# Iso_SPI_PHY.net
KiCad netlist of a schematic drawn in Altium Designer
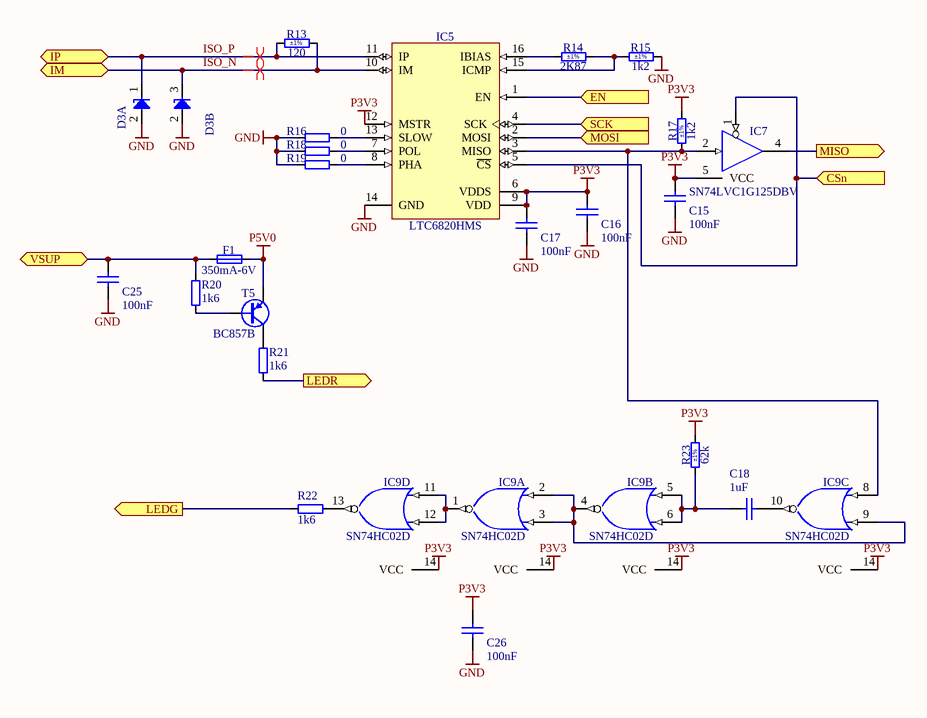
[diagram p0: Iso_SPI_PHY.SchDoc]

(export (version "E")
  (design (tool "Eeschema 10.0.6"))
  (components
    (comp (ref "C15")
      (value "100nF")
      (footprint "CAPC1005X55N")
      (description "Non-polarised capacitor")
      (fields
        (field (name "PART NUMBER") "CC0402_100NF_50V_10%_X7R")
        (field (name "VOLTAGE") "50V")
        (field (name "AUTHOR") "CERN DEM MR")
      )
      (libsource (lib "Capacitors") (part "Capacitor - non polarized"))
    )
    (comp (ref "C16")
      (value "100nF")
      (footprint "CAPC1005X55N")
      (description "Non-polarised capacitor")
      (fields
        (field (name "PART NUMBER") "CC0402_100NF_50V_10%_X7R")
        (field (name "VOLTAGE") "50V")
        (field (name "AUTHOR") "CERN DEM MR")
      )
      (libsource (lib "Capacitors") (part "Capacitor - non polarized"))
    )
    (comp (ref "C17")
      (value "100nF")
      (footprint "CAPC1005X55N")
      (description "Non-polarised capacitor")
      (fields
        (field (name "PART NUMBER") "CC0402_100NF_50V_10%_X7R")
        (field (name "VOLTAGE") "50V")
        (field (name "AUTHOR") "CERN DEM MR")
      )
      (libsource (lib "Capacitors") (part "Capacitor - non polarized"))
    )
    (comp (ref "C18")
      (value "1uF")
      (footprint "CAPC1608X87N")
      (description "Non-polarised capacitor")
      (fields
        (field (name "PART NUMBER") "CC0603_1UF_25V_10%_X7R")
        (field (name "VOLTAGE") "25V")
        (field (name "AUTHOR") "CERN DEM JLC")
      )
      (libsource (lib "Capacitors") (part "Capacitor - non polarized"))
    )
    (comp (ref "C25")
      (value "100nF")
      (footprint "CAPC1005X55N")
      (description "Non-polarised capacitor")
      (fields
        (field (name "PART NUMBER") "CC0402_100NF_50V_10%_X7R")
        (field (name "VOLTAGE") "50V")
        (field (name "AUTHOR") "CERN DEM MR")
      )
      (libsource (lib "Capacitors") (part "Capacitor - non polarized"))
    )
    (comp (ref "C26")
      (value "100nF")
      (footprint "CAPC1005X55N")
      (description "Non-polarised capacitor")
      (fields
        (field (name "PART NUMBER") "CC0402_100NF_50V_10%_X7R")
        (field (name "VOLTAGE") "50V")
        (field (name "AUTHOR") "CERN DEM MR")
      )
      (libsource (lib "Capacitors") (part "Capacitor - non polarized"))
    )
    (comp (ref "D3")
      (value "PESD3V3L5UY")
      (footprint "SOT65P210X110-6N")
      (description "Fivefold ESD Protection Diode Arrays")
      (fields
        (field (name "VOLTAGE") "3.3V")
        (field (name "POWER") "200W")
        (field (name "AUTHOR") "CERN DEM WB")
      )
      (libsource (lib "ICs And Semiconductors") (part "PESD Array 5diodes 6pins Common anode2"))
    )
    (comp (ref "F1")
      (value "350mA-6V")
      (footprint "FUSR_TYCO_MICROSMD035F")
      (description "Fuse")
      (fields
        (field (name "PART NUMBER") "FUSR1210_TYCO_MICROSMD035F-2")
        (field (name "MANUFACTURER") "TYCO ELECTRONICS")
        (field (name "AUTHOR") "CERN DEM JLC")
      )
      (libsource (lib "Eletro-mechanical") (part "Fuse"))
    )
    (comp (ref "IC5")
      (value "LTC6820HMS")
      (footprint "SOP50P490X110-16N")
      (description "isoSPI Isolated Communications Interface")
      (fields (field (name "MANUFACTURER") "ANALOG DEVICES") (field (name "AUTHOR") "CERN DEM BC"))
      (libsource (lib "ICs And Semiconductors") (part "LTC6820xMS"))
    )
    (comp (ref "IC7")
      (value "SN74LVC1G125DBV")
      (footprint "SOT95P280X145-5N")
      (description "Single Bus Buffer Gate With 3-State Output")
      (fields (field (name "MANUFACTURER") "TEXAS INSTRUMENTS") (field (name "AUTHOR") "CERN DEM HF"))
      (libsource (lib "ICs And Semiconductors") (part "741G125"))
    )
    (comp (ref "IC9")
      (value "SN74HC02D")
      (footprint "SOIC127P600X175-14N")
      (description "Quad 2-Input NOR Gate")
      (fields (field (name "MANUFACTURER") "TEXAS INSTRUMENTS") (field (name "AUTHOR") "CERN DEM JLC"))
      (libsource (lib "ICs And Semiconductors") (part "7402"))
    )
    (comp (ref "R13")
      (value "120")
      (footprint "RESC1608X55N")
      (description "Resistor - 1%")
      (fields
        (field (name "TOLERANCE") "±1%")
        (field (name "PART NUMBER") "R0603_120R_1%_0.1W_100PPM")
        (field (name "POWER") "0.1W")
        (field (name "AUTHOR") "CERN DEM JLC")
      )
      (libsource (lib "Resistors") (part "Resistor - 1%"))
    )
    (comp (ref "R14")
      (value "2K87")
      (footprint "RESC1005X40N")
      (description "Resistor - 1%")
      (fields
        (field (name "TOLERANCE") "±1%")
        (field (name "PART NUMBER") "R0402_2K87_1%_0.063W_100PPM")
        (field (name "POWER") "0.063W")
        (field (name "AUTHOR") "CERN DEM BC")
      )
      (libsource (lib "Resistors") (part "Resistor - 1%"))
    )
    (comp (ref "R15")
      (value "1k2")
      (footprint "RESC1005X40N")
      (description "Resistor - 1%")
      (fields
        (field (name "TOLERANCE") "±1%")
        (field (name "PART NUMBER") "R0402_1K2_1%_0.0625W_100PPM")
        (field (name "POWER") "0.0625W")
        (field (name "AUTHOR") "CERN DEM JLC")
      )
      (libsource (lib "Resistors") (part "Resistor - 1%"))
    )
    (comp (ref "R16")
      (value "0")
      (footprint "RESC1005X40N")
      (description "Resistor")
      (fields
        (field (name "PART NUMBER") "R0402_0R_JUMPER")
        (field (name "MANUFACTURER") "GENERIC")
        (field (name "AUTHOR") "CERN DEM JLC")
      )
      (libsource (lib "Resistors") (part "Resistor"))
    )
    (comp (ref "R17")
      (value "1k2")
      (footprint "RESC1005X40N")
      (description "Resistor - 1%")
      (fields
        (field (name "TOLERANCE") "±1%")
        (field (name "PART NUMBER") "R0402_1K2_1%_0.0625W_100PPM")
        (field (name "POWER") "0.0625W")
        (field (name "AUTHOR") "CERN DEM JLC")
      )
      (libsource (lib "Resistors") (part "Resistor - 1%"))
    )
    (comp (ref "R18")
      (value "0")
      (footprint "RESC1005X40N")
      (description "Resistor")
      (fields
        (field (name "PART NUMBER") "R0402_0R_JUMPER")
        (field (name "MANUFACTURER") "GENERIC")
        (field (name "AUTHOR") "CERN DEM JLC")
      )
      (libsource (lib "Resistors") (part "Resistor"))
    )
    (comp (ref "R19")
      (value "0")
      (footprint "RESC1005X40N")
      (description "Resistor")
      (fields
        (field (name "PART NUMBER") "R0402_0R_JUMPER")
        (field (name "MANUFACTURER") "GENERIC")
        (field (name "AUTHOR") "CERN DEM JLC")
      )
      (libsource (lib "Resistors") (part "Resistor"))
    )
    (comp (ref "R20")
      (value "1k6")
      (footprint "RESC1005X40N")
      (description "Resistor - 1%")
      (fields
        (field (name "PART NUMBER") "R0402_1K6_1%_0.0625W_100PPM")
        (field (name "POWER") "0.0625W")
        (field (name "AUTHOR") "CERN DEM JLC")
      )
      (libsource (lib "Resistors") (part "Resistor - 1%"))
    )
    (comp (ref "R21")
      (value "1k6")
      (footprint "RESC1005X40N")
      (description "Resistor - 1%")
      (fields
        (field (name "PART NUMBER") "R0402_1K6_1%_0.0625W_100PPM")
        (field (name "POWER") "0.0625W")
        (field (name "AUTHOR") "CERN DEM JLC")
      )
      (libsource (lib "Resistors") (part "Resistor - 1%"))
    )
    (comp (ref "R22")
      (value "1k6")
      (footprint "RESC1005X40N")
      (description "Resistor - 1%")
      (fields
        (field (name "PART NUMBER") "R0402_1K6_1%_0.0625W_100PPM")
        (field (name "POWER") "0.0625W")
        (field (name "AUTHOR") "CERN DEM JLC")
      )
      (libsource (lib "Resistors") (part "Resistor - 1%"))
    )
    (comp (ref "R23")
      (value "62k")
      (footprint "RESC1608X55N")
      (description "Resistor - 1%")
      (fields
        (field (name "TOLERANCE") "±1%")
        (field (name "PART NUMBER") "R0603_62K_1%_0.1W_100PPM")
        (field (name "POWER") "0.1W")
        (field (name "AUTHOR") "CERN DEM JLC")
      )
      (libsource (lib "Resistors") (part "Resistor - 1%"))
    )
    (comp (ref "T5")
      (value "BC857B")
      (footprint "SOT95P230X110-3N")
      (description "PNP Transistor")
      (fields (field (name "MANUFACTURER") "NXP SEMICONDUCTORS") (field (name "AUTHOR") "CERN DEM JLC"))
      (libsource (lib "ICs And Semiconductors") (part "PNP B1 E2 C3"))
    )
  )
  (nets
    (net (code "1") (name "/CSn") (class "Default")
      (node (ref "IC5") (pin "5") (pinfunction "~{CS}_5") (pintype "bidirectional"))
      (node (ref "IC7") (pin "1") (pinfunction "~{G}_1") (pintype "input"))
    )
    (net (code "2") (name "/EN") (class "Default")
      (node (ref "IC5") (pin "1") (pinfunction "EN_1") (pintype "input"))
    )
    (net (code "3") (name "/ISO_N") (class "Default")
      (node (ref "D3") (pin "3") (pinfunction "C_3") (pintype "passive"))
      (node (ref "IC5") (pin "10") (pinfunction "IM_10") (pintype "bidirectional"))
      (node (ref "R13") (pin "2") (pinfunction "2_2") (pintype "passive"))
    )
    (net (code "4") (name "/ISO_P") (class "Default")
      (node (ref "D3") (pin "1") (pinfunction "C_1") (pintype "passive"))
      (node (ref "IC5") (pin "11") (pinfunction "IP_11") (pintype "bidirectional"))
      (node (ref "R13") (pin "1") (pinfunction "1_1") (pintype "passive"))
    )
    (net (code "5") (name "/LEDG") (class "Default")
      (node (ref "R22") (pin "2") (pinfunction "2_2") (pintype "passive"))
    )
    (net (code "6") (name "/LEDR") (class "Default")
      (node (ref "R21") (pin "1") (pinfunction "1_1") (pintype "passive"))
    )
    (net (code "7") (name "/MISO") (class "Default")
      (node (ref "IC7") (pin "4") (pinfunction "OUT_4") (pintype "tri_state"))
    )
    (net (code "8") (name "/MOSI") (class "Default")
      (node (ref "IC5") (pin "2") (pinfunction "MOSI_2") (pintype "bidirectional"))
    )
    (net (code "9") (name "/SCK") (class "Default")
      (node (ref "IC5") (pin "4") (pinfunction "SCK_4") (pintype "bidirectional"))
    )
    (net (code "10") (name "/VSUP") (class "Default")
      (node (ref "C25") (pin "2") (pinfunction "2_2") (pintype "passive"))
      (node (ref "F1") (pin "1") (pinfunction "1_1") (pintype "passive"))
      (node (ref "R20") (pin "2") (pinfunction "2_2") (pintype "passive"))
    )
    (net (code "11") (name "GND") (class "Default")
      (node (ref "C15") (pin "1") (pinfunction "1_1") (pintype "passive"))
      (node (ref "C16") (pin "1") (pinfunction "1_1") (pintype "passive"))
      (node (ref "C17") (pin "1") (pinfunction "1_1") (pintype "passive"))
      (node (ref "C25") (pin "1") (pinfunction "1_1") (pintype "passive"))
      (node (ref "C26") (pin "1") (pinfunction "1_1") (pintype "passive"))
      (node (ref "D3") (pin "2") (pinfunction "A_2") (pintype "passive"))
      (node (ref "IC5") (pin "14") (pinfunction "GND_14") (pintype "power_in"))
      (node (ref "IC7") (pin "3") (pinfunction "GND_3") (pintype "power_in"))
      (node (ref "IC9") (pin "7") (pinfunction "GND_7") (pintype "power_in"))
      (node (ref "R15") (pin "2") (pinfunction "2_2") (pintype "passive"))
      (node (ref "R16") (pin "1") (pinfunction "1_1") (pintype "passive"))
      (node (ref "R18") (pin "1") (pinfunction "1_1") (pintype "passive"))
      (node (ref "R19") (pin "1") (pinfunction "1_1") (pintype "passive"))
    )
    (net (code "12") (name "Net-(IC5-IBIAS)") (class "Default")
      (node (ref "IC5") (pin "16") (pinfunction "IBIAS_16") (pintype "input"))
      (node (ref "R14") (pin "1") (pinfunction "1_1") (pintype "passive"))
    )
    (net (code "13") (name "Net-(IC5-ICMP)") (class "Default")
      (node (ref "IC5") (pin "15") (pinfunction "ICMP_15") (pintype "input"))
      (node (ref "R14") (pin "2") (pinfunction "2_2") (pintype "passive"))
      (node (ref "R15") (pin "1") (pinfunction "1_1") (pintype "passive"))
    )
    (net (code "14") (name "Net-(IC5-MISO)") (class "Default")
      (node (ref "IC5") (pin "3") (pinfunction "MISO_3") (pintype "bidirectional"))
      (node (ref "IC7") (pin "2") (pinfunction "IN_2") (pintype "input"))
      (node (ref "IC9") (pin "8") (pinfunction "A_8") (pintype "input"))
      (node (ref "R17") (pin "1") (pinfunction "1_1") (pintype "passive"))
    )
    (net (code "15") (name "Net-(IC5-PHA)") (class "Default")
      (node (ref "IC5") (pin "8") (pinfunction "PHA_8") (pintype "input"))
      (node (ref "R19") (pin "2") (pinfunction "2_2") (pintype "passive"))
    )
    (net (code "16") (name "Net-(IC5-POL)") (class "Default")
      (node (ref "IC5") (pin "7") (pinfunction "POL_7") (pintype "input"))
      (node (ref "R18") (pin "2") (pinfunction "2_2") (pintype "passive"))
    )
    (net (code "17") (name "Net-(IC5-SLOW)") (class "Default")
      (node (ref "IC5") (pin "13") (pinfunction "SLOW_13") (pintype "input"))
      (node (ref "R16") (pin "2") (pinfunction "2_2") (pintype "passive"))
    )
    (net (code "18") (name "Net-(IC9A-A)") (class "Default")
      (node (ref "IC9") (pin "2") (pinfunction "A_2") (pintype "input"))
      (node (ref "IC9") (pin "3") (pinfunction "B_3") (pintype "input"))
      (node (ref "IC9") (pin "4") (pinfunction "~{O}_4") (pintype "output"))
      (node (ref "IC9") (pin "9") (pinfunction "B_9") (pintype "input"))
    )
    (net (code "19") (name "Net-(IC9A-~{O})") (class "Default")
      (node (ref "IC9") (pin "1") (pinfunction "~{O}_1") (pintype "output"))
      (node (ref "IC9") (pin "11") (pinfunction "A_11") (pintype "input"))
      (node (ref "IC9") (pin "12") (pinfunction "B_12") (pintype "input"))
    )
    (net (code "20") (name "Net-(IC9B-A)") (class "Default")
      (node (ref "C18") (pin "2") (pinfunction "2_2") (pintype "passive"))
      (node (ref "IC9") (pin "5") (pinfunction "A_5") (pintype "input"))
      (node (ref "IC9") (pin "6") (pinfunction "B_6") (pintype "input"))
      (node (ref "R23") (pin "1") (pinfunction "1_1") (pintype "passive"))
    )
    (net (code "21") (name "Net-(IC9C-~{O})") (class "Default")
      (node (ref "C18") (pin "1") (pinfunction "1_1") (pintype "passive"))
      (node (ref "IC9") (pin "10") (pinfunction "~{O}_10") (pintype "output"))
    )
    (net (code "22") (name "Net-(IC9D-~{O})") (class "Default")
      (node (ref "IC9") (pin "13") (pinfunction "~{O}_13") (pintype "output"))
      (node (ref "R22") (pin "1") (pinfunction "1_1") (pintype "passive"))
    )
    (net (code "23") (name "Net-(T5-B)") (class "Default")
      (node (ref "R20") (pin "1") (pinfunction "1_1") (pintype "passive"))
      (node (ref "T5") (pin "1") (pinfunction "B_1") (pintype "passive"))
    )
    (net (code "24") (name "Net-(T5-C)") (class "Default")
      (node (ref "R21") (pin "2") (pinfunction "2_2") (pintype "passive"))
      (node (ref "T5") (pin "3") (pinfunction "C_3") (pintype "passive"))
    )
    (net (code "25") (name "P3V3") (class "Default")
      (node (ref "C15") (pin "2") (pinfunction "2_2") (pintype "passive"))
      (node (ref "C16") (pin "2") (pinfunction "2_2") (pintype "passive"))
      (node (ref "C17") (pin "2") (pinfunction "2_2") (pintype "passive"))
      (node (ref "C26") (pin "2") (pinfunction "2_2") (pintype "passive"))
      (node (ref "IC5") (pin "12") (pinfunction "MSTR_12") (pintype "input"))
      (node (ref "IC5") (pin "6") (pinfunction "VDDS_6") (pintype "power_in"))
      (node (ref "IC5") (pin "9") (pinfunction "VDD_9") (pintype "power_in"))
      (node (ref "IC7") (pin "5") (pinfunction "VCC_5") (pintype "power_in"))
      (node (ref "IC9") (pin "14") (pinfunction "VCC_14") (pintype "power_in"))
      (node (ref "R17") (pin "2") (pinfunction "2_2") (pintype "passive"))
      (node (ref "R23") (pin "2") (pinfunction "2_2") (pintype "passive"))
    )
    (net (code "26") (name "P5V0") (class "Default")
      (node (ref "F1") (pin "2") (pinfunction "2_2") (pintype "passive"))
      (node (ref "T5") (pin "2") (pinfunction "E_2") (pintype "passive"))
    )
  )
)
